# PT-SA.net
KiCad netlist of a schematic drawn in EAGLE
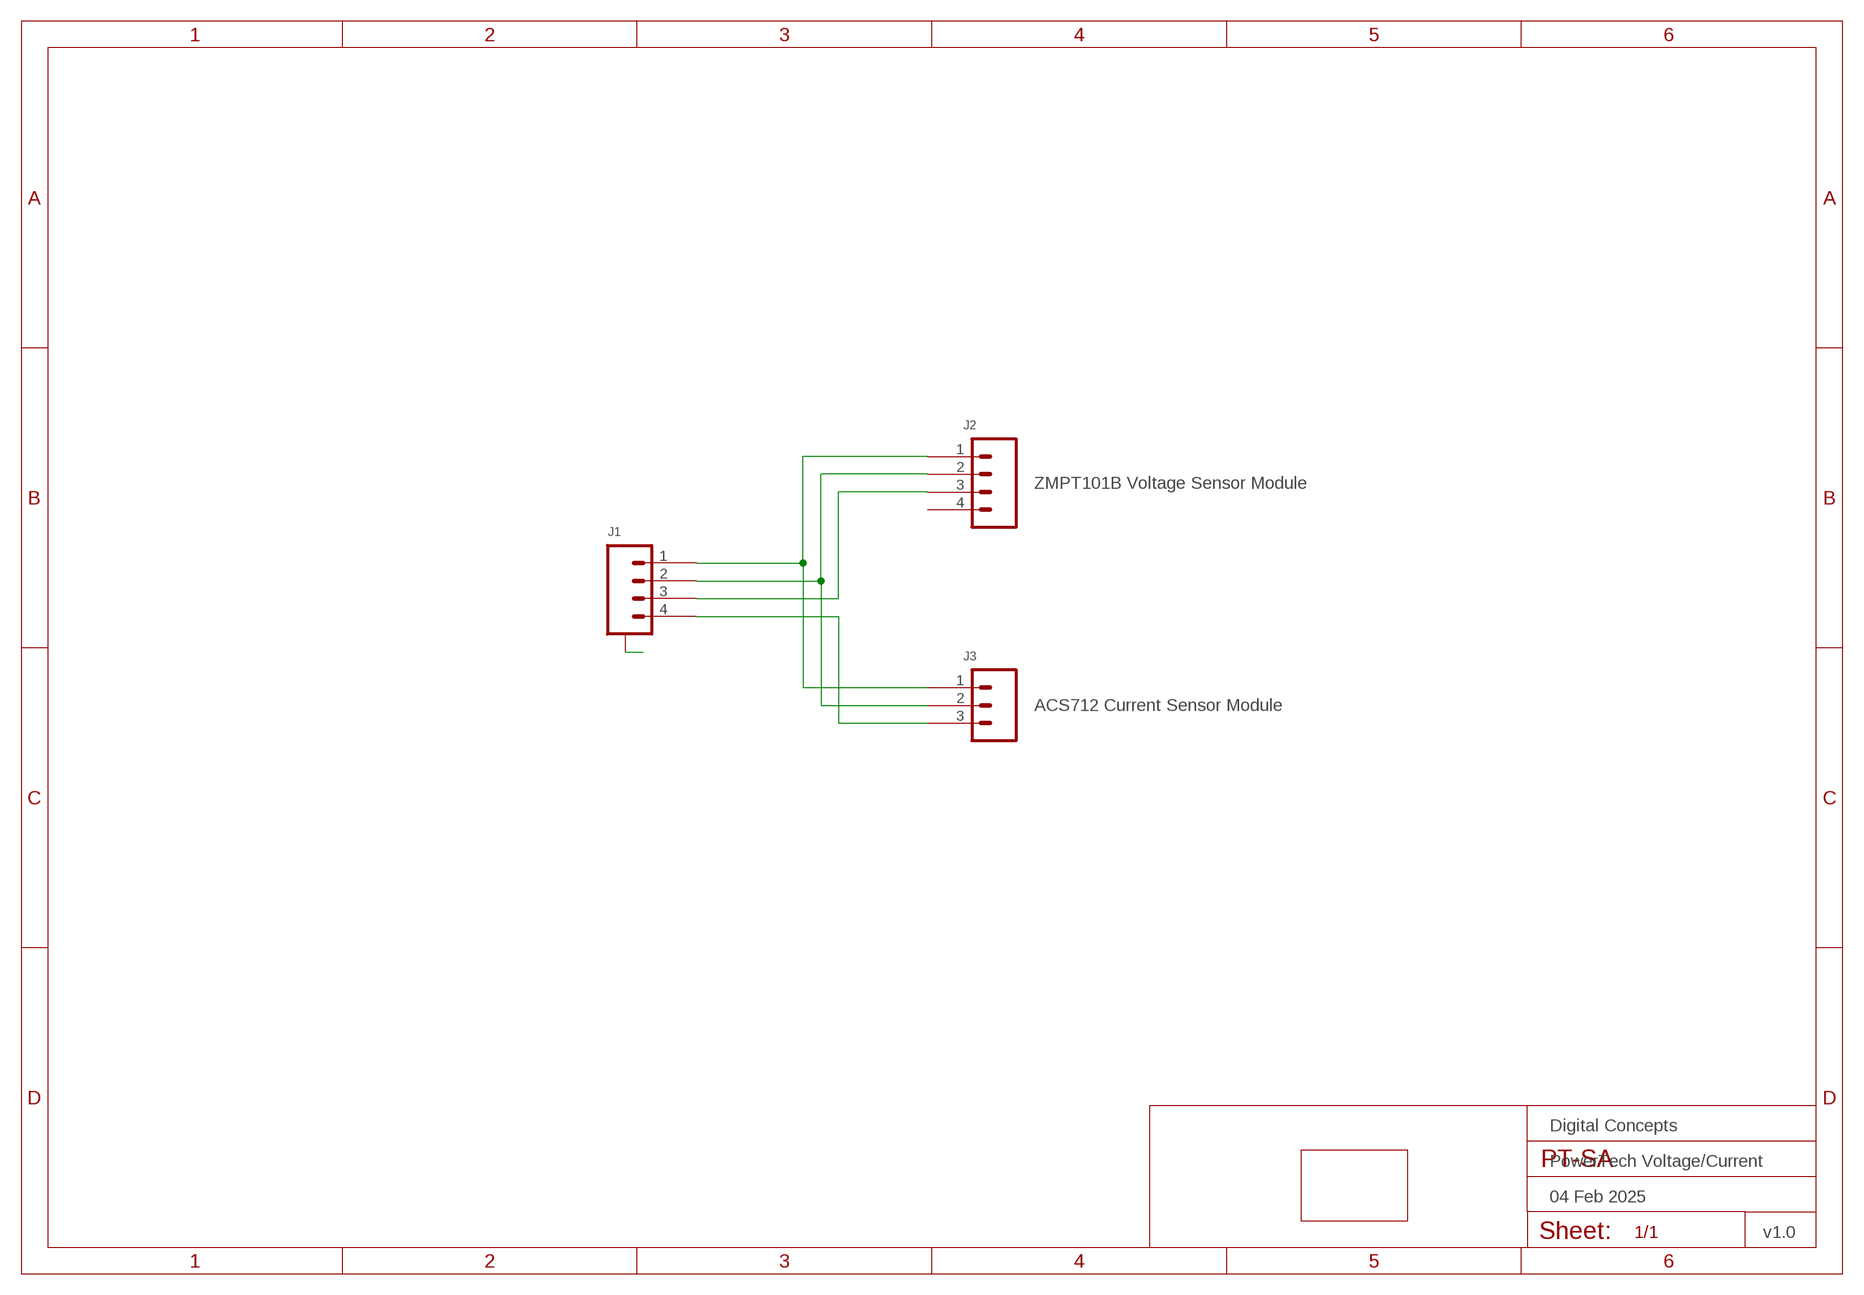
[diagram p0: schematic, sheet 1]

(export (version "E")
  (design (tool "Eeschema 10.0.6"))
  (components
    (comp (ref "J1")
      (value "JST-SH1.0-4-SMD-HORIZONTAL")
      (footprint "eagle-import:JST-SH1.0-4-HORIZONTAL")
      (libsource (lib "eagle-import") (part "JST-SH1.0-4-SMD-HORIZONTAL"))
    )
    (comp (ref "J2")
      (value "ZMPT101B Voltage Sensor Module")
      (footprint "eagle-import:CONN_04-GENERIC")
      (libsource (lib "eagle-import") (part "HEADER-1X4-GENERIC"))
    )
    (comp (ref "J3")
      (value "ACS712 Current Sensor Module")
      (footprint "eagle-import:CONN_03-GENERIC")
      (libsource (lib "eagle-import") (part "HEADER-1X3-GENERIC"))
    )
    (comp (ref "PCB1")
      (value "POWERTECH-SOCKET")
      (footprint "eagle-import:PCB-POWERTECH")
      (libsource (lib "eagle-import") (part "POWERTECH-SOCKET"))
    )
  )
  (nets
    (net (code "1") (name "Net-(J1-A-PadA@1)") (class "Default")
      (node (ref "J1") (pin "A@1") (pinfunction "A_A@1") (pintype "power_in"))
      (node (ref "J1") (pin "A@4") (pinfunction "A_A@4") (pintype "power_in"))
    )
    (net (code "2") (name "Net-(J1-Pad1)") (class "Default")
      (node (ref "J1") (pin "1") (pinfunction "1_1") (pintype "passive"))
      (node (ref "J2") (pin "1") (pinfunction "1_1") (pintype "passive"))
      (node (ref "J3") (pin "1") (pinfunction "1_1") (pintype "passive"))
    )
    (net (code "3") (name "Net-(J1-Pad2)") (class "Default")
      (node (ref "J1") (pin "2") (pinfunction "2_2") (pintype "passive"))
      (node (ref "J2") (pin "2") (pinfunction "2_2") (pintype "passive"))
      (node (ref "J3") (pin "2") (pinfunction "2_2") (pintype "passive"))
    )
    (net (code "4") (name "Net-(J1-Pad3)") (class "Default")
      (node (ref "J1") (pin "3") (pinfunction "3_3") (pintype "passive"))
      (node (ref "J2") (pin "3") (pinfunction "3_3") (pintype "passive"))
    )
    (net (code "5") (name "Net-(J1-Pad4)") (class "Default")
      (node (ref "J1") (pin "4") (pinfunction "4_4") (pintype "passive"))
      (node (ref "J3") (pin "3") (pinfunction "3_3") (pintype "passive"))
    )
    (net (code "6") (name "unconnected-(J2-Pad4)") (class "Default")
      (node (ref "J2") (pin "4") (pinfunction "4_4") (pintype "passive"))
    )
  )
)
